# Tenk.net
KiCad netlist of a schematic drawn in Altium Designer
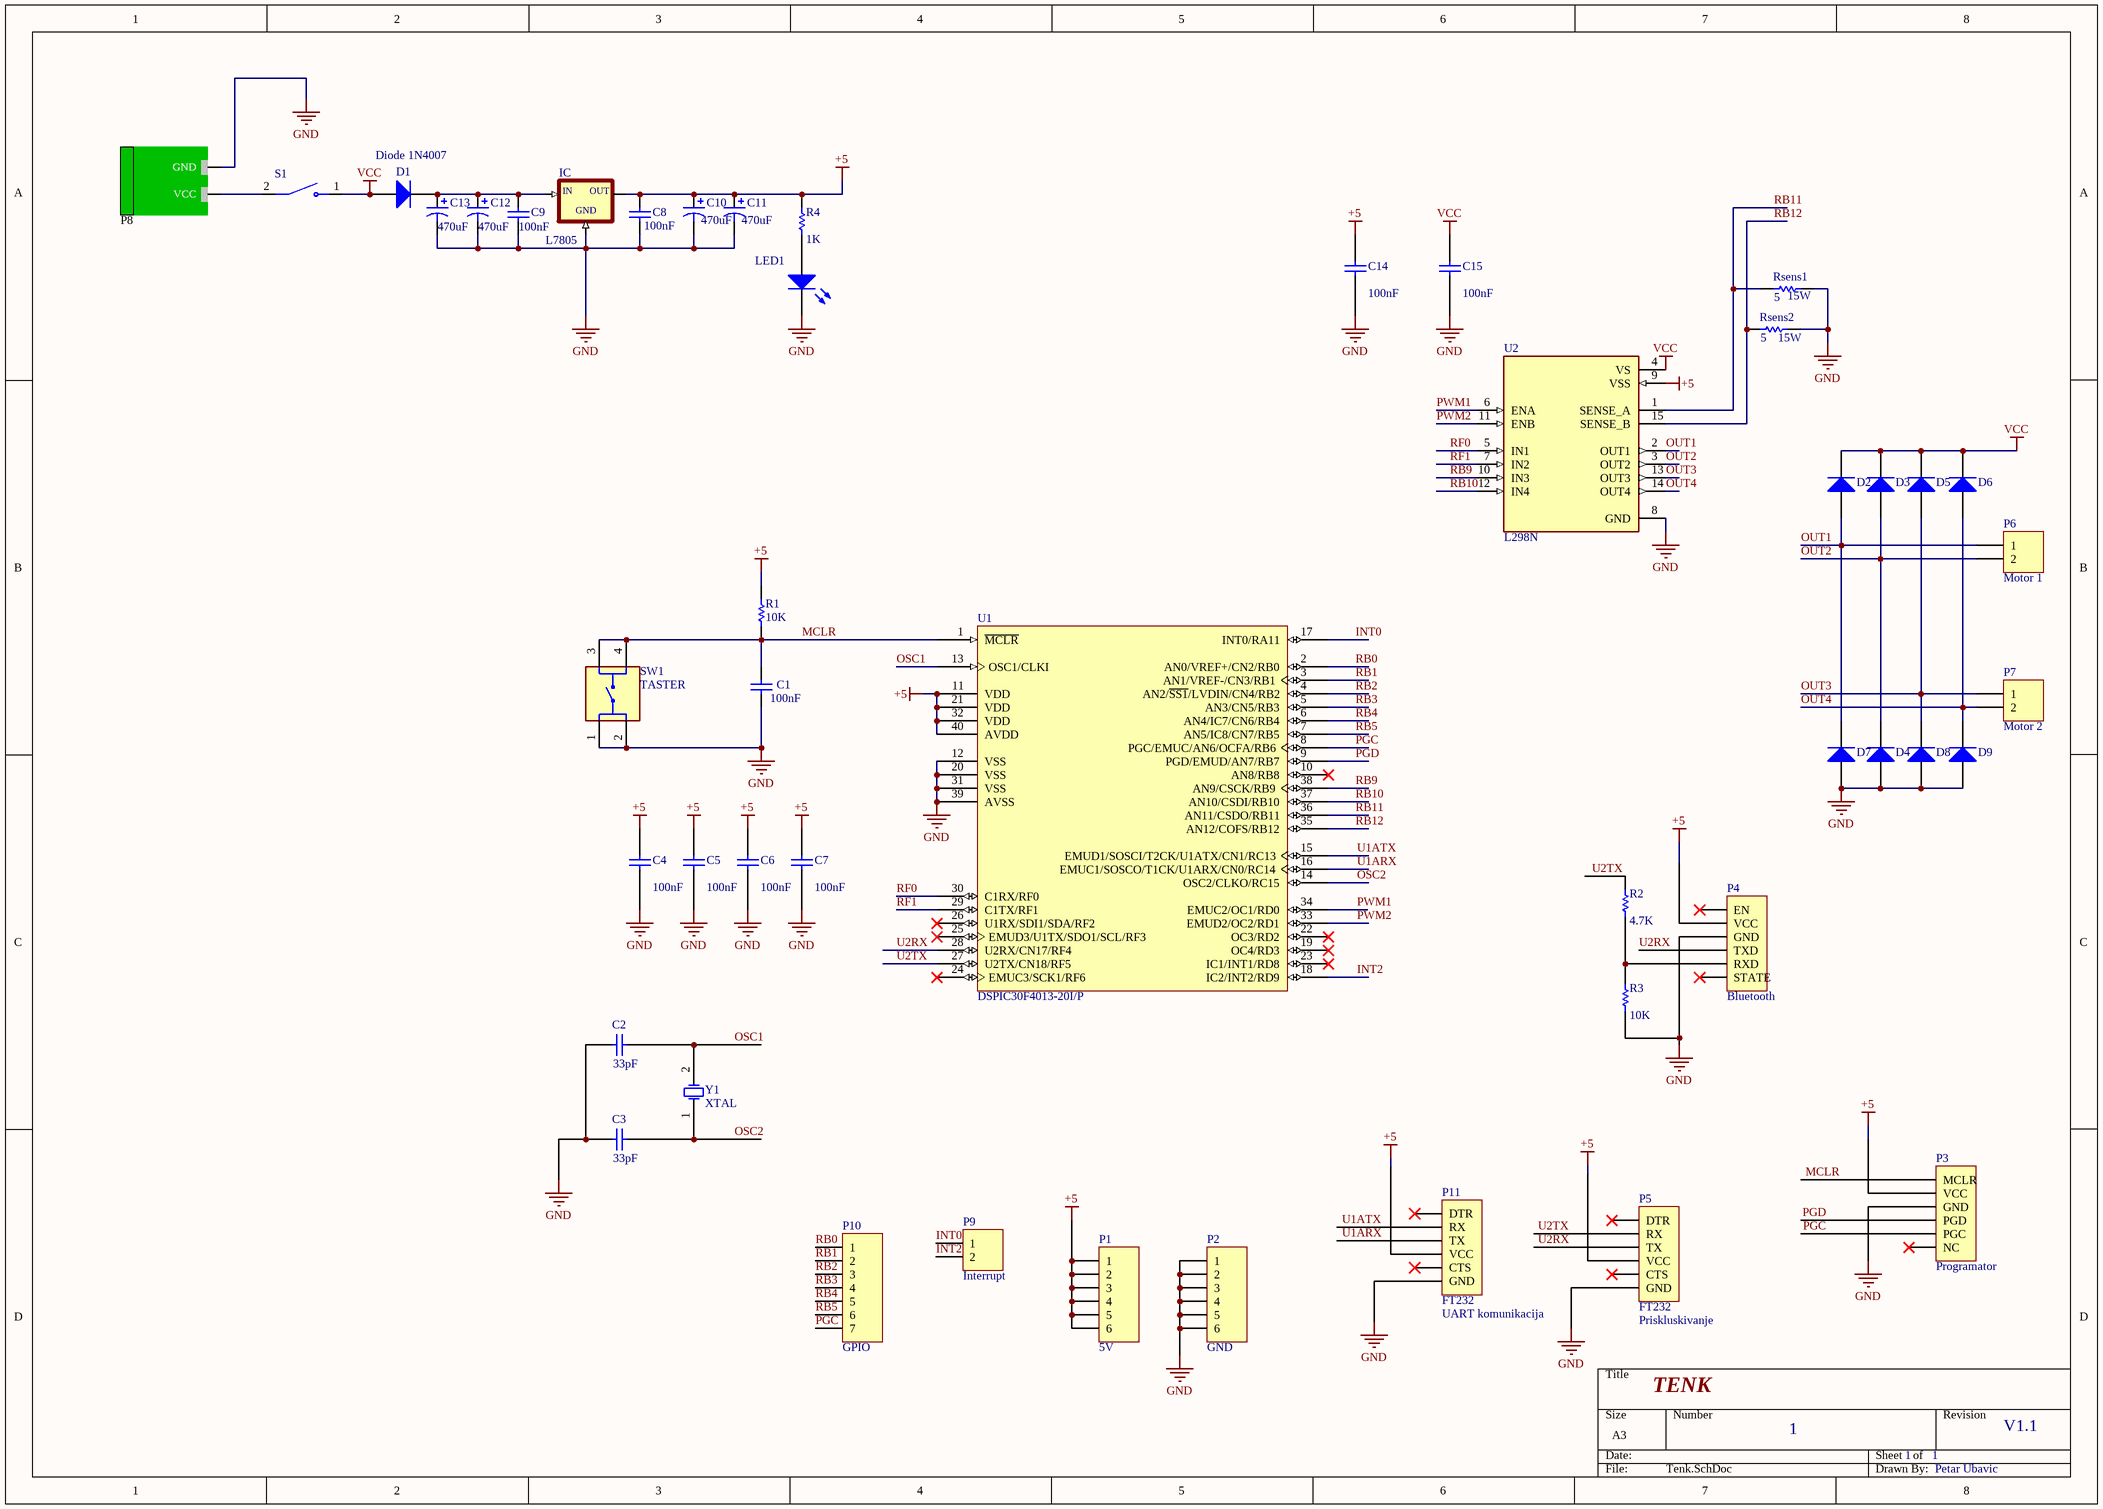
[diagram p0: Tenk.SchDoc]

(export (version "E")
  (design (tool "Eeschema 10.0.6"))
  (components
    (comp (ref "C1")
      (value "100nF")
      (footprint "CAP200")
      (description "Capacitor")
      (fields (field (name "Comment") "Cap") (field (name "PUBLISHER") "Altium Limited"))
      (libsource (lib "Miscellaneous Devices") (part "Cap"))
    )
    (comp (ref "C2")
      (value "33pF")
      (footprint "CAP200")
      (description "Capacitor")
      (fields (field (name "Comment") "Cap") (field (name "PUBLISHER") "Altium Limited"))
      (libsource (lib "Miscellaneous Devices") (part "Cap"))
    )
    (comp (ref "C3")
      (value "33pF")
      (footprint "CAP200")
      (description "Capacitor")
      (fields (field (name "Comment") "Cap") (field (name "PUBLISHER") "Altium Limited"))
      (libsource (lib "Miscellaneous Devices") (part "Cap"))
    )
    (comp (ref "C4")
      (value "100nF")
      (footprint "CAP200")
      (description "Capacitor")
      (fields (field (name "Comment") "Cap") (field (name "PUBLISHER") "Altium Limited"))
      (libsource (lib "Miscellaneous Devices") (part "Cap"))
    )
    (comp (ref "C5")
      (value "100nF")
      (footprint "CAP200")
      (description "Capacitor")
      (fields (field (name "Comment") "Cap") (field (name "PUBLISHER") "Altium Limited"))
      (libsource (lib "Miscellaneous Devices") (part "Cap"))
    )
    (comp (ref "C6")
      (value "100nF")
      (footprint "CAP200")
      (description "Capacitor")
      (fields (field (name "Comment") "Cap") (field (name "PUBLISHER") "Altium Limited"))
      (libsource (lib "Miscellaneous Devices") (part "Cap"))
    )
    (comp (ref "C7")
      (value "100nF")
      (footprint "CAP200")
      (description "Capacitor")
      (fields (field (name "Comment") "Cap") (field (name "PUBLISHER") "Altium Limited"))
      (libsource (lib "Miscellaneous Devices") (part "Cap"))
    )
    (comp (ref "C8")
      (value "100nF")
      (footprint "CAP200")
      (description "Capacitor")
      (fields (field (name "Comment") "Cap") (field (name "PUBLISHER") "Altium Limited"))
      (libsource (lib "Miscellaneous Devices") (part "Cap"))
    )
    (comp (ref "C9")
      (value "100nF")
      (footprint "CAP200")
      (description "Capacitor")
      (fields (field (name "Comment") "Cap") (field (name "PUBLISHER") "Altium Limited"))
      (libsource (lib "Miscellaneous Devices") (part "Cap"))
    )
    (comp (ref "C10")
      (value "470uF")
      (footprint "RAD4")
      (description "Polarized Capacitor (Radial)")
      (fields (field (name "Comment") "Cap Pol1") (field (name "PUBLISHER") "Altium Limited"))
      (libsource (lib "Miscellaneous Devices") (part "Cap Pol1"))
    )
    (comp (ref "C11")
      (value "470uF")
      (footprint "RAD4")
      (description "Polarized Capacitor (Radial)")
      (fields (field (name "Comment") "Cap Pol1") (field (name "PUBLISHER") "Altium Limited"))
      (libsource (lib "Miscellaneous Devices") (part "Cap Pol1"))
    )
    (comp (ref "C12")
      (value "470uF")
      (footprint "RAD4")
      (description "Polarized Capacitor (Radial)")
      (fields (field (name "Comment") "Cap Pol1") (field (name "PUBLISHER") "Altium Limited"))
      (libsource (lib "Miscellaneous Devices") (part "Cap Pol1"))
    )
    (comp (ref "C13")
      (value "470uF")
      (footprint "RAD4")
      (description "Polarized Capacitor (Radial)")
      (fields (field (name "Comment") "Cap Pol1") (field (name "PUBLISHER") "Altium Limited"))
      (libsource (lib "Miscellaneous Devices") (part "Cap Pol1"))
    )
    (comp (ref "C14")
      (value "100nF")
      (footprint "CAP200")
      (description "Capacitor")
      (fields (field (name "Comment") "Cap") (field (name "PUBLISHER") "Altium Limited"))
      (libsource (lib "Miscellaneous Devices") (part "Cap"))
    )
    (comp (ref "C15")
      (value "100nF")
      (footprint "CAP200")
      (description "Capacitor")
      (fields (field (name "Comment") "Cap") (field (name "PUBLISHER") "Altium Limited"))
      (libsource (lib "Miscellaneous Devices") (part "Cap"))
    )
    (comp (ref "D1")
      (value "Diode 1N4007")
      (footprint "DIODE400")
      (description "1 Amp General Purpose Rectifier")
      (fields (field (name "PUBLISHER") "Altium Limited"))
      (libsource (lib "Miscellaneous Devices") (part "Diode 1N4007"))
    )
    (comp (ref "D2")
      (value "Diode 1N5402")
      (footprint "DIODE400")
      (description "3 Amp General Purpose Rectifier")
      (fields (field (name "PUBLISHER") "Altium Limited"))
      (libsource (lib "Miscellaneous Devices") (part "Diode 1N5402"))
    )
    (comp (ref "D3")
      (value "Diode 1N5402")
      (footprint "DIODE400")
      (description "3 Amp General Purpose Rectifier")
      (fields (field (name "PUBLISHER") "Altium Limited"))
      (libsource (lib "Miscellaneous Devices") (part "Diode 1N5402"))
    )
    (comp (ref "D4")
      (value "Diode 1N5402")
      (footprint "DIODE400")
      (description "3 Amp General Purpose Rectifier")
      (fields (field (name "PUBLISHER") "Altium Limited"))
      (libsource (lib "Miscellaneous Devices") (part "Diode 1N5402"))
    )
    (comp (ref "D5")
      (value "Diode 1N5402")
      (footprint "DIODE400")
      (description "3 Amp General Purpose Rectifier")
      (fields (field (name "PUBLISHER") "Altium Limited"))
      (libsource (lib "Miscellaneous Devices") (part "Diode 1N5402"))
    )
    (comp (ref "D6")
      (value "Diode 1N5402")
      (footprint "DIODE400")
      (description "3 Amp General Purpose Rectifier")
      (fields (field (name "PUBLISHER") "Altium Limited"))
      (libsource (lib "Miscellaneous Devices") (part "Diode 1N5402"))
    )
    (comp (ref "D7")
      (value "Diode 1N5402")
      (footprint "DIODE400")
      (description "3 Amp General Purpose Rectifier")
      (fields (field (name "PUBLISHER") "Altium Limited"))
      (libsource (lib "Miscellaneous Devices") (part "Diode 1N5402"))
    )
    (comp (ref "D8")
      (value "Diode 1N5402")
      (footprint "DIODE400")
      (description "3 Amp General Purpose Rectifier")
      (fields (field (name "PUBLISHER") "Altium Limited"))
      (libsource (lib "Miscellaneous Devices") (part "Diode 1N5402"))
    )
    (comp (ref "D9")
      (value "Diode 1N5402")
      (footprint "DIODE400")
      (description "3 Amp General Purpose Rectifier")
      (fields (field (name "PUBLISHER") "Altium Limited"))
      (libsource (lib "Miscellaneous Devices") (part "Diode 1N5402"))
    )
    (comp (ref "IC")
      (value "L7805")
      (footprint "78XXS")
      (description "Linear Voltage Regulator IC 1 Output 1.5A D2PAK")
      (fields (field (name "MF") "STMicroelectronics"))
      (libsource (lib "L7805") (part "L7805"))
    )
    (comp (ref "LED1")
      (value "GREEN")
      (footprint "LED_2")
      (description "Typical RED GaAs LED")
      (fields (field (name "PUBLISHER") "Altium Limited"))
      (libsource (lib "Miscellaneous Devices") (part "LED1"))
    )
    (comp (ref "P1")
      (value "5V")
      (footprint "HEADER_6")
      (description "Header, 6-Pin")
      (fields (field (name "PUBLISHER") "Altium Limited"))
      (libsource (lib "Miscellaneous Connectors") (part "Header 6"))
    )
    (comp (ref "P2")
      (value "GND")
      (footprint "HEADER_6")
      (description "Header, 6-Pin")
      (fields (field (name "PUBLISHER") "Altium Limited"))
      (libsource (lib "Miscellaneous Connectors") (part "Header 6"))
    )
    (comp (ref "P3")
      (value "Programator")
      (footprint "HEADER_6")
      (description "Header, 6-Pin")
      (fields (field (name "PUBLISHER") "Altium Limited"))
      (libsource (lib "Miscellaneous Connectors") (part "Header 6"))
    )
    (comp (ref "P4")
      (value "Bluetooth")
      (footprint "HEADER_6")
      (description "Header, 6-Pin")
      (fields (field (name "PUBLISHER") "Altium Limited"))
      (libsource (lib "Miscellaneous Connectors") (part "Header 6"))
    )
    (comp (ref "P5")
      (value "FT232")
      (footprint "HEADER_6")
      (description "Header, 6-Pin")
      (fields (field (name "PUBLISHER") "Altium Limited"))
      (libsource (lib "Miscellaneous Connectors") (part "Header 6"))
    )
    (comp (ref "P6")
      (value "Motor 1")
      (footprint "HDR1X2")
      (description "Header, 2-Pin")
      (fields (field (name "PUBLISHER") "Altium Limited"))
      (libsource (lib "Miscellaneous Connectors") (part "Header 2"))
    )
    (comp (ref "P7")
      (value "Motor 2")
      (footprint "HDR1X2")
      (description "Header, 2-Pin")
      (fields (field (name "PUBLISHER") "Altium Limited"))
      (libsource (lib "Miscellaneous Connectors") (part "Header 2"))
    )
    (comp (ref "P8")
      (value "2EDGRC-5.08-02P-14-00A(H)")
      (footprint "PWR_Con")
      (description "TERM BLOCK HDR 2POS 90DEG 5.08MM")
      (libsource (lib "Electro_Mechanical") (part "00000002"))
    )
    (comp (ref "P9")
      (value "Interrupt")
      (footprint "HDR1X2")
      (description "Header, 2-Pin")
      (fields (field (name "PUBLISHER") "Altium Limited"))
      (libsource (lib "Miscellaneous Connectors") (part "Header 2"))
    )
    (comp (ref "P10")
      (value "GPIO")
      (footprint "HDR1X7")
      (description "Header, 7-Pin")
      (fields (field (name "PUBLISHER") "Altium Limited"))
      (libsource (lib "Miscellaneous Connectors") (part "Header 7"))
    )
    (comp (ref "P11")
      (value "FT232")
      (footprint "HEADER_6")
      (description "Header, 6-Pin")
      (fields (field (name "PUBLISHER") "Altium Limited"))
      (libsource (lib "Miscellaneous Connectors") (part "Header 6"))
    )
    (comp (ref "R1")
      (value "10K")
      (footprint "RES400")
      (description "Resistor")
      (fields (field (name "Comment") "Res1") (field (name "PUBLISHER") "Altium Limited"))
      (libsource (lib "Miscellaneous Devices") (part "Res1"))
    )
    (comp (ref "R2")
      (value "4.7K")
      (footprint "RES400")
      (description "Resistor")
      (fields (field (name "Comment") "Res1") (field (name "PUBLISHER") "Altium Limited"))
      (libsource (lib "Miscellaneous Devices") (part "Res1"))
    )
    (comp (ref "R3")
      (value "10K")
      (footprint "RES400")
      (description "Resistor")
      (fields (field (name "Comment") "Res1") (field (name "PUBLISHER") "Altium Limited"))
      (libsource (lib "Miscellaneous Devices") (part "Res1"))
    )
    (comp (ref "R4")
      (value "1K")
      (footprint "RES400")
      (description "Resistor")
      (fields (field (name "Comment") "Res1") (field (name "PUBLISHER") "Altium Limited"))
      (libsource (lib "Miscellaneous Devices") (part "Res1"))
    )
    (comp (ref "Rsens1")
      (value "15W")
      (footprint "Rsens")
      (description "Resistor")
      (fields (field (name "ALTIUM_VALUE") "5") (field (name "PUBLISHER") "Altium Limited"))
      (libsource (lib "Miscellaneous Devices") (part "Res1"))
    )
    (comp (ref "Rsens2")
      (value "15W")
      (footprint "Rsens")
      (description "Resistor")
      (fields (field (name "ALTIUM_VALUE") "5") (field (name "PUBLISHER") "Altium Limited"))
      (libsource (lib "Miscellaneous Devices") (part "Res1"))
    )
    (comp (ref "S1")
      (value "~")
      (footprint "SW_RB141C1100")
      (description "Rocker Switches 15A 125VAC, OFF-ON, Black Rocker, No Markings")
      (fields (field (name "MP") "RB141C1100") (field (name "MF") "e-switch inc"))
      (libsource (lib "RB141C1100") (part "RB141C1100"))
    )
    (comp (ref "SW1")
      (value "TASTER")
      (footprint "SW_1825910-6-4")
      (description "Switch Tactile OFF (ON) SPST Round Button PC Pins 0.05A 24VDC 100000Cycles 1.57N Thru-Hole Loose")
      (fields (field (name "MP") "1825910-6"))
      (libsource (lib "1825910-6") (part "1825910-6"))
    )
    (comp (ref "U1")
      (value "DSPIC30F4013-20I/P")
      (footprint "PDIP600-P40")
      (fields (field (name "PUBLISHER") "Altium Limited"))
      (libsource (lib "Microchip DSC 16-Bit dsPIC30F") (part "DSPIC30F4013-20I/P"))
    )
    (comp (ref "U2")
      (value "L298N")
      (footprint "TO127P2020X500X2100-15")
      (description "Dual Full Bridge Motor Driver 15-Pin(15+Tab) MULTIWATT V Tube")
      (libsource (lib "L298N") (part "L298N"))
    )
    (comp (ref "Y1")
      (value "XTAL")
      (footprint "OSC_5")
      (description "Crystal Oscillator")
      (fields (field (name "PUBLISHER") "Altium Limited"))
      (libsource (lib "Miscellaneous Devices") (part "XTAL"))
    )
  )
  (nets
    (net (code "1") (name "+5") (class "Default")
      (node (ref "C10") (pin "1") (pinfunction "1_1") (pintype "passive"))
      (node (ref "C11") (pin "1") (pinfunction "1_1") (pintype "passive"))
      (node (ref "C14") (pin "2") (pinfunction "2_2") (pintype "passive"))
      (node (ref "C4") (pin "2") (pinfunction "2_2") (pintype "passive"))
      (node (ref "C5") (pin "2") (pinfunction "2_2") (pintype "passive"))
      (node (ref "C6") (pin "2") (pinfunction "2_2") (pintype "passive"))
      (node (ref "C7") (pin "2") (pinfunction "2_2") (pintype "passive"))
      (node (ref "C8") (pin "2") (pinfunction "2_2") (pintype "passive"))
      (node (ref "IC") (pin "OUT") (pinfunction "OUT_OUT") (pintype "passive"))
      (node (ref "P1") (pin "1") (pinfunction "1_1") (pintype "passive"))
      (node (ref "P1") (pin "2") (pinfunction "2_2") (pintype "passive"))
      (node (ref "P1") (pin "3") (pinfunction "3_3") (pintype "passive"))
      (node (ref "P1") (pin "4") (pinfunction "4_4") (pintype "passive"))
      (node (ref "P1") (pin "5") (pinfunction "5_5") (pintype "passive"))
      (node (ref "P1") (pin "6") (pinfunction "6_6") (pintype "passive"))
      (node (ref "P11") (pin "4") (pinfunction "4_4") (pintype "passive"))
      (node (ref "P3") (pin "2") (pinfunction "2_2") (pintype "passive"))
      (node (ref "P4") (pin "2") (pinfunction "2_2") (pintype "passive"))
      (node (ref "P5") (pin "4") (pinfunction "4_4") (pintype "passive"))
      (node (ref "R1") (pin "2") (pinfunction "2_2") (pintype "passive"))
      (node (ref "R4") (pin "2") (pinfunction "2_2") (pintype "passive"))
      (node (ref "U1") (pin "11") (pinfunction "VDD_11") (pintype "power_in"))
      (node (ref "U1") (pin "21") (pinfunction "VDD_21") (pintype "power_in"))
      (node (ref "U1") (pin "32") (pinfunction "VDD_32") (pintype "power_in"))
      (node (ref "U1") (pin "40") (pinfunction "AVDD_40") (pintype "power_in"))
      (node (ref "U2") (pin "9") (pinfunction "VSS_9") (pintype "input"))
    )
    (net (code "2") (name "/INT0") (class "Default")
      (node (ref "P9") (pin "1") (pinfunction "1_1") (pintype "passive"))
      (node (ref "U1") (pin "17") (pinfunction "INT0/RA11_17") (pintype "bidirectional"))
    )
    (net (code "3") (name "/INT2") (class "Default")
      (node (ref "P9") (pin "2") (pinfunction "2_2") (pintype "passive"))
      (node (ref "U1") (pin "18") (pinfunction "IC2/INT2/RD9_18") (pintype "bidirectional"))
    )
    (net (code "4") (name "/MCLR") (class "Default")
      (node (ref "C1") (pin "2") (pinfunction "2_2") (pintype "passive"))
      (node (ref "P3") (pin "1") (pinfunction "1_1") (pintype "passive"))
      (node (ref "R1") (pin "1") (pinfunction "1_1") (pintype "passive"))
      (node (ref "SW1") (pin "3") (pinfunction "3_3") (pintype "passive"))
      (node (ref "SW1") (pin "4") (pinfunction "4_4") (pintype "passive"))
      (node (ref "U1") (pin "1") (pinfunction "~{MCLR}_1") (pintype "input"))
    )
    (net (code "5") (name "/OSC1") (class "Default")
      (node (ref "C2") (pin "2") (pinfunction "2_2") (pintype "passive"))
      (node (ref "U1") (pin "13") (pinfunction "OSC1/CLKI_13") (pintype "input"))
      (node (ref "Y1") (pin "2") (pinfunction "OSC2_2") (pintype "passive"))
    )
    (net (code "6") (name "/OSC2") (class "Default")
      (node (ref "C3") (pin "2") (pinfunction "2_2") (pintype "passive"))
      (node (ref "U1") (pin "14") (pinfunction "OSC2/CLKO/RC15_14") (pintype "bidirectional"))
      (node (ref "Y1") (pin "1") (pinfunction "OSC1_1") (pintype "passive"))
    )
    (net (code "7") (name "/OUT1") (class "Default")
      (node (ref "D2") (pin "1") (pinfunction "A_1") (pintype "passive"))
      (node (ref "D7") (pin "2") (pinfunction "K_2") (pintype "passive"))
      (node (ref "P6") (pin "1") (pinfunction "1_1") (pintype "passive"))
      (node (ref "U2") (pin "2") (pinfunction "OUT1_2") (pintype "output"))
    )
    (net (code "8") (name "/OUT2") (class "Default")
      (node (ref "D3") (pin "1") (pinfunction "A_1") (pintype "passive"))
      (node (ref "D4") (pin "2") (pinfunction "K_2") (pintype "passive"))
      (node (ref "P6") (pin "2") (pinfunction "2_2") (pintype "passive"))
      (node (ref "U2") (pin "3") (pinfunction "OUT2_3") (pintype "output"))
    )
    (net (code "9") (name "/OUT3") (class "Default")
      (node (ref "D5") (pin "1") (pinfunction "A_1") (pintype "passive"))
      (node (ref "D8") (pin "2") (pinfunction "K_2") (pintype "passive"))
      (node (ref "P7") (pin "1") (pinfunction "1_1") (pintype "passive"))
      (node (ref "U2") (pin "13") (pinfunction "OUT3_13") (pintype "output"))
    )
    (net (code "10") (name "/OUT4") (class "Default")
      (node (ref "D6") (pin "1") (pinfunction "A_1") (pintype "passive"))
      (node (ref "D9") (pin "2") (pinfunction "K_2") (pintype "passive"))
      (node (ref "P7") (pin "2") (pinfunction "2_2") (pintype "passive"))
      (node (ref "U2") (pin "14") (pinfunction "OUT4_14") (pintype "output"))
    )
    (net (code "11") (name "/PGC") (class "Default")
      (node (ref "P10") (pin "7") (pinfunction "7_7") (pintype "passive"))
      (node (ref "P3") (pin "5") (pinfunction "5_5") (pintype "passive"))
      (node (ref "U1") (pin "8") (pinfunction "PGC/EMUC/AN6/OCFA/RB6_8") (pintype "bidirectional"))
    )
    (net (code "12") (name "/PGD") (class "Default")
      (node (ref "P3") (pin "4") (pinfunction "4_4") (pintype "passive"))
      (node (ref "U1") (pin "9") (pinfunction "PGD/EMUD/AN7/RB7_9") (pintype "bidirectional"))
    )
    (net (code "13") (name "/PWM1") (class "Default")
      (node (ref "U1") (pin "34") (pinfunction "EMUC2/OC1/RD0_34") (pintype "bidirectional"))
      (node (ref "U2") (pin "6") (pinfunction "ENA_6") (pintype "input"))
    )
    (net (code "14") (name "/PWM2") (class "Default")
      (node (ref "U1") (pin "33") (pinfunction "EMUD2/OC2/RD1_33") (pintype "bidirectional"))
      (node (ref "U2") (pin "11") (pinfunction "ENB_11") (pintype "input"))
    )
    (net (code "15") (name "/RB0") (class "Default")
      (node (ref "P10") (pin "1") (pinfunction "1_1") (pintype "passive"))
      (node (ref "U1") (pin "2") (pinfunction "AN0/VREF+/CN2/RB0_2") (pintype "bidirectional"))
    )
    (net (code "16") (name "/RB1") (class "Default")
      (node (ref "P10") (pin "2") (pinfunction "2_2") (pintype "passive"))
      (node (ref "U1") (pin "3") (pinfunction "AN1/VREF-/CN3/RB1_3") (pintype "bidirectional"))
    )
    (net (code "17") (name "/RB2") (class "Default")
      (node (ref "P10") (pin "3") (pinfunction "3_3") (pintype "passive"))
      (node (ref "U1") (pin "4") (pinfunction "AN2/~{SS1}/LVDIN/CN4/RB2_4") (pintype "bidirectional"))
    )
    (net (code "18") (name "/RB3") (class "Default")
      (node (ref "P10") (pin "4") (pinfunction "4_4") (pintype "passive"))
      (node (ref "U1") (pin "5") (pinfunction "AN3/CN5/RB3_5") (pintype "bidirectional"))
    )
    (net (code "19") (name "/RB4") (class "Default")
      (node (ref "P10") (pin "5") (pinfunction "5_5") (pintype "passive"))
      (node (ref "U1") (pin "6") (pinfunction "AN4/IC7/CN6/RB4_6") (pintype "bidirectional"))
    )
    (net (code "20") (name "/RB5") (class "Default")
      (node (ref "P10") (pin "6") (pinfunction "6_6") (pintype "passive"))
      (node (ref "U1") (pin "7") (pinfunction "AN5/IC8/CN7/RB5_7") (pintype "bidirectional"))
    )
    (net (code "21") (name "/RB9") (class "Default")
      (node (ref "U1") (pin "38") (pinfunction "AN9/CSCK/RB9_38") (pintype "bidirectional"))
      (node (ref "U2") (pin "10") (pinfunction "IN3_10") (pintype "input"))
    )
    (net (code "22") (name "/RB10") (class "Default")
      (node (ref "U1") (pin "37") (pinfunction "AN10/CSDI/RB10_37") (pintype "bidirectional"))
      (node (ref "U2") (pin "12") (pinfunction "IN4_12") (pintype "input"))
    )
    (net (code "23") (name "/RB11") (class "Default")
      (node (ref "Rsens1") (pin "1") (pinfunction "1_1") (pintype "passive"))
      (node (ref "U1") (pin "36") (pinfunction "AN11/CSDO/RB11_36") (pintype "bidirectional"))
      (node (ref "U2") (pin "1") (pinfunction "SENSE_A_1") (pintype "passive"))
    )
    (net (code "24") (name "/RB12") (class "Default")
      (node (ref "Rsens2") (pin "1") (pinfunction "1_1") (pintype "passive"))
      (node (ref "U1") (pin "35") (pinfunction "AN12/COFS/RB12_35") (pintype "bidirectional"))
      (node (ref "U2") (pin "15") (pinfunction "SENSE_B_15") (pintype "passive"))
    )
    (net (code "25") (name "/RF0") (class "Default")
      (node (ref "U1") (pin "30") (pinfunction "C1RX/RF0_30") (pintype "bidirectional"))
      (node (ref "U2") (pin "5") (pinfunction "IN1_5") (pintype "input"))
    )
    (net (code "26") (name "/RF1") (class "Default")
      (node (ref "U1") (pin "29") (pinfunction "C1TX/RF1_29") (pintype "bidirectional"))
      (node (ref "U2") (pin "7") (pinfunction "IN2_7") (pintype "input"))
    )
    (net (code "27") (name "/U1ARX") (class "Default")
      (node (ref "P11") (pin "3") (pinfunction "3_3") (pintype "passive"))
      (node (ref "U1") (pin "16") (pinfunction "EMUC1/SOSCO/T1CK/U1ARX/CN0/RC14_16") (pintype "bidirectional"))
    )
    (net (code "28") (name "/U1ATX") (class "Default")
      (node (ref "P11") (pin "2") (pinfunction "2_2") (pintype "passive"))
      (node (ref "U1") (pin "15") (pinfunction "EMUD1/SOSCI/T2CK/U1ATX/CN1/RC13_15") (pintype "bidirectional"))
    )
    (net (code "29") (name "/U2RX") (class "Default")
      (node (ref "P4") (pin "4") (pinfunction "4_4") (pintype "passive"))
      (node (ref "P5") (pin "3") (pinfunction "3_3") (pintype "passive"))
      (node (ref "U1") (pin "28") (pinfunction "U2RX/CN17/RF4_28") (pintype "bidirectional"))
    )
    (net (code "30") (name "/U2TX") (class "Default")
      (node (ref "P5") (pin "2") (pinfunction "2_2") (pintype "passive"))
      (node (ref "R2") (pin "2") (pinfunction "2_2") (pintype "passive"))
      (node (ref "U1") (pin "27") (pinfunction "U2TX/CN18/RF5_27") (pintype "bidirectional"))
    )
    (net (code "31") (name "GND") (class "Default")
      (node (ref "C1") (pin "1") (pinfunction "1_1") (pintype "passive"))
      (node (ref "C10") (pin "2") (pinfunction "2_2") (pintype "passive"))
      (node (ref "C11") (pin "2") (pinfunction "2_2") (pintype "passive"))
      (node (ref "C12") (pin "2") (pinfunction "2_2") (pintype "passive"))
      (node (ref "C13") (pin "2") (pinfunction "2_2") (pintype "passive"))
      (node (ref "C14") (pin "1") (pinfunction "1_1") (pintype "passive"))
      (node (ref "C15") (pin "1") (pinfunction "1_1") (pintype "passive"))
      (node (ref "C2") (pin "1") (pinfunction "1_1") (pintype "passive"))
      (node (ref "C3") (pin "1") (pinfunction "1_1") (pintype "passive"))
      (node (ref "C4") (pin "1") (pinfunction "1_1") (pintype "passive"))
      (node (ref "C5") (pin "1") (pinfunction "1_1") (pintype "passive"))
      (node (ref "C6") (pin "1") (pinfunction "1_1") (pintype "passive"))
      (node (ref "C7") (pin "1") (pinfunction "1_1") (pintype "passive"))
      (node (ref "C8") (pin "1") (pinfunction "1_1") (pintype "passive"))
      (node (ref "C9") (pin "1") (pinfunction "1_1") (pintype "passive"))
      (node (ref "D4") (pin "1") (pinfunction "A_1") (pintype "passive"))
      (node (ref "D7") (pin "1") (pinfunction "A_1") (pintype "passive"))
      (node (ref "D8") (pin "1") (pinfunction "A_1") (pintype "passive"))
      (node (ref "D9") (pin "1") (pinfunction "A_1") (pintype "passive"))
      (node (ref "IC") (pin "GND") (pinfunction "GND_GND") (pintype "input"))
      (node (ref "LED1") (pin "2") (pinfunction "K_2") (pintype "passive"))
      (node (ref "P11") (pin "6") (pinfunction "6_6") (pintype "passive"))
      (node (ref "P2") (pin "1") (pinfunction "1_1") (pintype "passive"))
      (node (ref "P2") (pin "2") (pinfunction "2_2") (pintype "passive"))
      (node (ref "P2") (pin "3") (pinfunction "3_3") (pintype "passive"))
      (node (ref "P2") (pin "4") (pinfunction "4_4") (pintype "passive"))
      (node (ref "P2") (pin "5") (pinfunction "5_5") (pintype "passive"))
      (node (ref "P2") (pin "6") (pinfunction "6_6") (pintype "passive"))
      (node (ref "P3") (pin "3") (pinfunction "3_3") (pintype "passive"))
      (node (ref "P4") (pin "3") (pinfunction "3_3") (pintype "passive"))
      (node (ref "P5") (pin "6") (pinfunction "6_6") (pintype "passive"))
      (node (ref "P8") (pin "1") (pinfunction "GND_1") (pintype "passive"))
      (node (ref "R3") (pin "1") (pinfunction "1_1") (pintype "passive"))
      (node (ref "Rsens1") (pin "2") (pinfunction "2_2") (pintype "passive"))
      (node (ref "Rsens2") (pin "2") (pinfunction "2_2") (pintype "passive"))
      (node (ref "SW1") (pin "1") (pinfunction "1_1") (pintype "passive"))
      (node (ref "SW1") (pin "2") (pinfunction "2_2") (pintype "passive"))
      (node (ref "U1") (pin "12") (pinfunction "VSS_12") (pintype "power_in"))
      (node (ref "U1") (pin "20") (pinfunction "VSS_20") (pintype "power_in"))
      (node (ref "U1") (pin "31") (pinfunction "VSS_31") (pintype "power_in"))
      (node (ref "U1") (pin "39") (pinfunction "AVSS_39") (pintype "power_in"))
      (node (ref "U2") (pin "8") (pinfunction "GND_8") (pintype "power_in"))
    )
    (net (code "32") (name "Net-(D1-K)") (class "Default")
      (node (ref "C12") (pin "1") (pinfunction "1_1") (pintype "passive"))
      (node (ref "C13") (pin "1") (pinfunction "1_1") (pintype "passive"))
      (node (ref "C9") (pin "2") (pinfunction "2_2") (pintype "passive"))
      (node (ref "D1") (pin "2") (pinfunction "K_2") (pintype "passive"))
      (node (ref "IC") (pin "IN") (pinfunction "IN_IN") (pintype "input"))
    )
    (net (code "33") (name "Net-(LED1-A)") (class "Default")
      (node (ref "LED1") (pin "1") (pinfunction "A_1") (pintype "passive"))
      (node (ref "R4") (pin "1") (pinfunction "1_1") (pintype "passive"))
    )
    (net (code "34") (name "Net-(P4-Pad5)") (class "Default")
      (node (ref "P4") (pin "5") (pinfunction "5_5") (pintype "passive"))
      (node (ref "R2") (pin "1") (pinfunction "1_1") (pintype "passive"))
      (node (ref "R3") (pin "2") (pinfunction "2_2") (pintype "passive"))
    )
    (net (code "35") (name "Net-(P8-VCC)") (class "Default")
      (node (ref "P8") (pin "2") (pinfunction "VCC_2") (pintype "passive"))
      (node (ref "S1") (pin "2") (pinfunction "2_2") (pintype "passive"))
    )
    (net (code "36") (name "VCC") (class "Default")
      (node (ref "C15") (pin "2") (pinfunction "2_2") (pintype "passive"))
      (node (ref "D1") (pin "1") (pinfunction "A_1") (pintype "passive"))
      (node (ref "D2") (pin "2") (pinfunction "K_2") (pintype "passive"))
      (node (ref "D3") (pin "2") (pinfunction "K_2") (pintype "passive"))
      (node (ref "D5") (pin "2") (pinfunction "K_2") (pintype "passive"))
      (node (ref "D6") (pin "2") (pinfunction "K_2") (pintype "passive"))
      (node (ref "S1") (pin "1") (pinfunction "1_1") (pintype "passive"))
      (node (ref "U2") (pin "4") (pinfunction "VS_4") (pintype "power_in"))
    )
    (net (code "37") (name "unconnected-(P3-Pad6)") (class "Default")
      (node (ref "P3") (pin "6") (pinfunction "6_6") (pintype "passive+no_connect"))
    )
    (net (code "38") (name "unconnected-(P4-Pad1)") (class "Default")
      (node (ref "P4") (pin "1") (pinfunction "1_1") (pintype "passive+no_connect"))
    )
    (net (code "39") (name "unconnected-(P4-Pad6)") (class "Default")
      (node (ref "P4") (pin "6") (pinfunction "6_6") (pintype "passive+no_connect"))
    )
    (net (code "40") (name "unconnected-(P5-Pad1)") (class "Default")
      (node (ref "P5") (pin "1") (pinfunction "1_1") (pintype "passive+no_connect"))
    )
    (net (code "41") (name "unconnected-(P5-Pad5)") (class "Default")
      (node (ref "P5") (pin "5") (pinfunction "5_5") (pintype "passive+no_connect"))
    )
    (net (code "42") (name "unconnected-(P11-Pad1)") (class "Default")
      (node (ref "P11") (pin "1") (pinfunction "1_1") (pintype "passive+no_connect"))
    )
    (net (code "43") (name "unconnected-(P11-Pad5)") (class "Default")
      (node (ref "P11") (pin "5") (pinfunction "5_5") (pintype "passive+no_connect"))
    )
    (net (code "44") (name "unconnected-(U1-AN8{slash}RB8-Pad10)") (class "Default")
      (node (ref "U1") (pin "10") (pinfunction "AN8/RB8_10") (pintype "bidirectional+no_connect"))
    )
    (net (code "45") (name "unconnected-(U1-EMUC3{slash}SCK1{slash}RF6-Pad24)") (class "Default")
      (node (ref "U1") (pin "24") (pinfunction "EMUC3/SCK1/RF6_24") (pintype "bidirectional+no_connect"))
    )
    (net (code "46") (name "unconnected-(U1-EMUD3{slash}U1TX{slash}SDO1{slash}SCL{slash}RF3-Pad25)") (class "Default")
      (node (ref "U1") (pin "25") (pinfunction "EMUD3/U1TX/SDO1/SCL/RF3_25") (pintype "bidirectional+no_connect"))
    )
    (net (code "47") (name "unconnected-(U1-IC1{slash}INT1{slash}RD8-Pad23)") (class "Default")
      (node (ref "U1") (pin "23") (pinfunction "IC1/INT1/RD8_23") (pintype "bidirectional+no_connect"))
    )
    (net (code "48") (name "unconnected-(U1-OC3{slash}RD2-Pad22)") (class "Default")
      (node (ref "U1") (pin "22") (pinfunction "OC3/RD2_22") (pintype "bidirectional+no_connect"))
    )
    (net (code "49") (name "unconnected-(U1-OC4{slash}RD3-Pad19)") (class "Default")
      (node (ref "U1") (pin "19") (pinfunction "OC4/RD3_19") (pintype "bidirectional+no_connect"))
    )
    (net (code "50") (name "unconnected-(U1-U1RX{slash}SDI1{slash}SDA{slash}RF2-Pad26)") (class "Default")
      (node (ref "U1") (pin "26") (pinfunction "U1RX/SDI1/SDA/RF2_26") (pintype "bidirectional+no_connect"))
    )
  )
)
